# MCU.net
KiCad netlist of a schematic drawn in Altium Designer
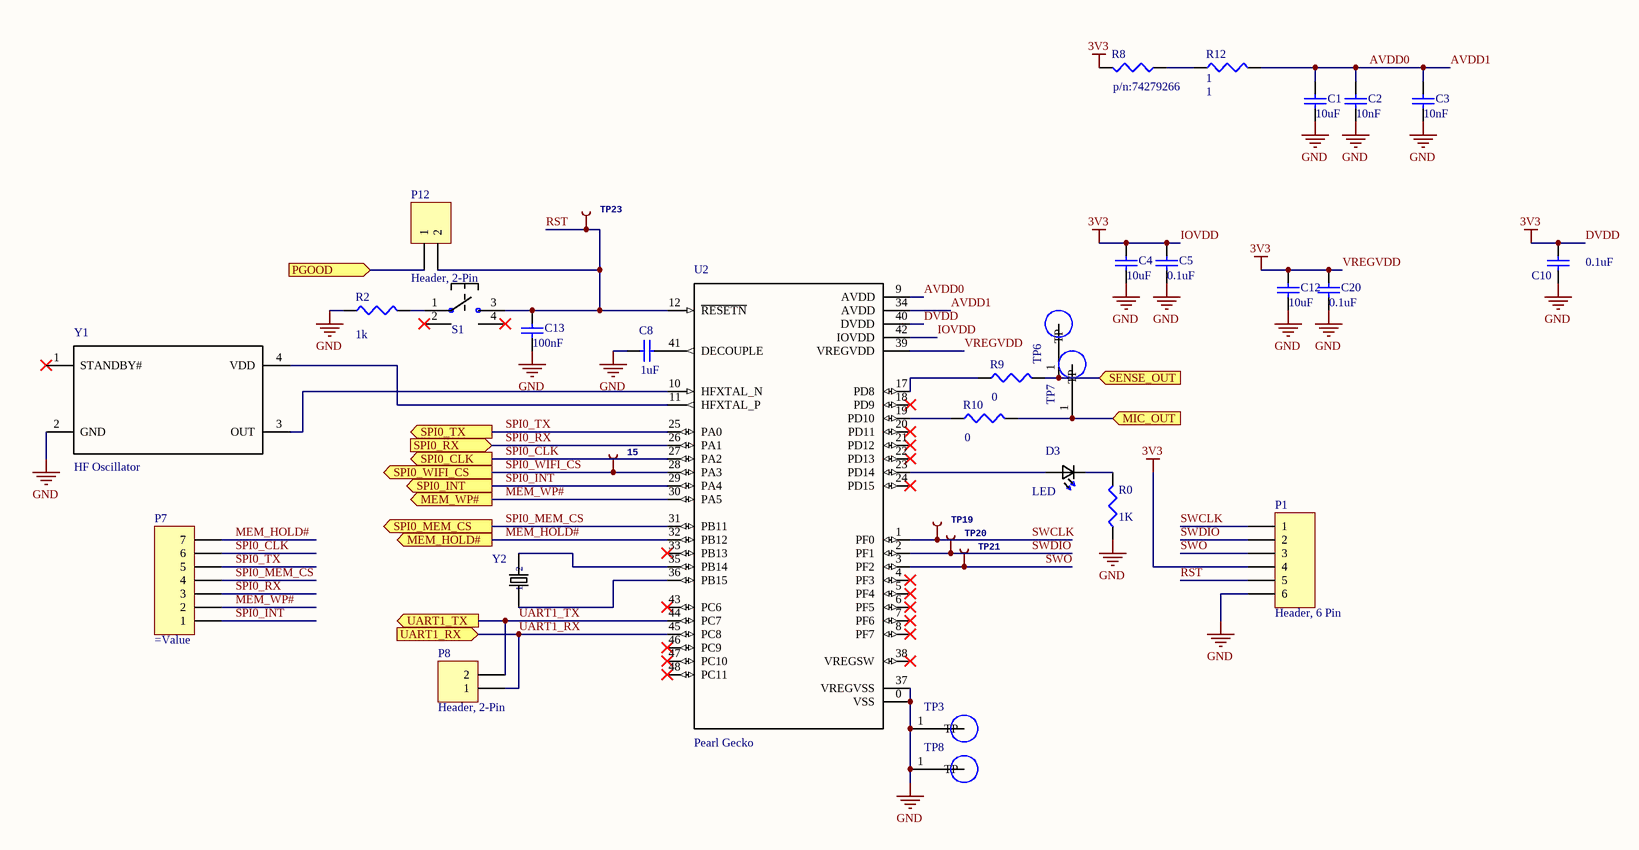
[diagram p0: MCU.SchDoc]

(export (version "E")
  (design (tool "Eeschema 10.0.6"))
  (components
    (comp (ref "15")
      (value "SparkFun Test Points")
      (footprint "PAD.02X.02")
      (libsource (lib "SparkFun-Connectors") (part "TEST-POINT2"))
    )
    (comp (ref "C1")
      (value "10uF")
      (footprint "1608[0603]")
      (description "Capacitor (Semiconductor SIM Model)")
      (fields (field (name "PUBLISHER") "Altium Limited"))
      (libsource (lib "Miscellaneous Devices") (part "Cap Semi"))
    )
    (comp (ref "C2")
      (value "10nF")
      (footprint "1608[0603]")
      (description "Capacitor (Semiconductor SIM Model)")
      (fields (field (name "PUBLISHER") "Altium Limited"))
      (libsource (lib "Miscellaneous Devices") (part "Cap Semi"))
    )
    (comp (ref "C3")
      (value "10nF")
      (footprint "1608[0603]")
      (description "Capacitor (Semiconductor SIM Model)")
      (fields (field (name "PUBLISHER") "Altium Limited"))
      (libsource (lib "Miscellaneous Devices") (part "Cap Semi"))
    )
    (comp (ref "C4")
      (value "10uF")
      (footprint "1608[0603]")
      (description "Capacitor (Semiconductor SIM Model)")
      (fields (field (name "PUBLISHER") "Altium Limited"))
      (libsource (lib "Miscellaneous Devices") (part "Cap Semi"))
    )
    (comp (ref "C5")
      (value "0.1uF")
      (footprint "1608[0603]")
      (description "Capacitor (Semiconductor SIM Model)")
      (fields (field (name "PUBLISHER") "Altium Limited"))
      (libsource (lib "Miscellaneous Devices") (part "Cap Semi"))
    )
    (comp (ref "C8")
      (value "1uF")
      (footprint "1608[0603]")
      (description "Capacitor (Semiconductor SIM Model)")
      (fields (field (name "PUBLISHER") "Altium Limited"))
      (libsource (lib "Miscellaneous Devices") (part "Cap Semi"))
    )
    (comp (ref "C10")
      (value "0.1uF")
      (footprint "1608[0603]")
      (description "Capacitor (Semiconductor SIM Model)")
      (fields (field (name "PUBLISHER") "Altium Limited"))
      (libsource (lib "Miscellaneous Devices") (part "Cap Semi"))
    )
    (comp (ref "C12")
      (value "10uF")
      (footprint "1608[0603]")
      (description "Capacitor (Semiconductor SIM Model)")
      (fields
        (field (name "MANUFACTURER") "Samsung")
        (field (name "MANUFACTURER PART NUMBER") "CL10B106MQ8NRNC")
        (field (name "PUBLISHER") "Altium Limited")
      )
      (libsource (lib "Miscellaneous Devices") (part "Cap Semi"))
    )
    (comp (ref "C13")
      (value "100nF")
      (footprint "1608[0603]")
      (description "Capacitor (Semiconductor SIM Model)")
      (fields (field (name "PUBLISHER") "Altium Limited"))
      (libsource (lib "Miscellaneous Devices") (part "Cap Semi"))
    )
    (comp (ref "C20")
      (value "0.1uF")
      (footprint "1608[0603]")
      (description "Capacitor (Semiconductor SIM Model)")
      (fields (field (name "PUBLISHER") "Altium Limited"))
      (libsource (lib "Miscellaneous Devices") (part "Cap Semi"))
    )
    (comp (ref "D3")
      (value "LED")
      (footprint "0603_TLMO1100-GS08(Primary)")
      (description "Orange 0603 160Â° 80 mcd 2.1 V 30 mA Non Diffused Surface Mount LED")
      (fields (field (name "MP") "TLMO1100-GS08") (field (name "DIGI-KEY_PART_NUMBER") "751-1174-1-ND"))
      (libsource (lib "LowPower_3ER_Parts") (part "TLMO1100-GS08"))
    )
    (comp (ref "P1")
      (value "Header, 6 Pin")
      (footprint "HDR1X6")
      (description "Header, 6-Pin")
      (fields (field (name "PUBLISHER") "Altium Limited"))
      (libsource (lib "Miscellaneous Connectors") (part "Header 6"))
    )
    (comp (ref "P7")
      (value "~")
      (footprint "HDR1X7")
      (description "Header, 7-Pin")
      (fields (field (name "PUBLISHER") "Altium Limited"))
      (libsource (lib "Miscellaneous Connectors") (part "Header 7"))
    )
    (comp (ref "P8")
      (value "Header, 2-Pin")
      (footprint "HDR1X2")
      (fields (field (name "PUBLISHER") "Altium Limited"))
      (libsource (lib "Miscellaneous Connectors") (part "Header 2"))
    )
    (comp (ref "P12")
      (value "Header, 2-Pin")
      (footprint "HDR1X2")
      (fields (field (name "PUBLISHER") "Altium Limited"))
      (libsource (lib "") (part "Header 2_1"))
    )
    (comp (ref "R0")
      (value "1K")
      (footprint "J1-0603")
      (description "Resistor")
      (fields (field (name "PUBLISHER") "Altium Limited"))
      (libsource (lib "Miscellaneous Devices") (part "Res3"))
    )
    (comp (ref "R2")
      (value "1k")
      (footprint "J1-0603")
      (description "Resistor")
      (fields (field (name "PUBLISHER") "Altium Limited"))
      (libsource (lib "Miscellaneous Devices") (part "Res3"))
    )
    (comp (ref "R8")
      (value "p/n:74279266")
      (footprint "J1-0603")
      (description "Resistor")
      (fields (field (name "Comment") "Ferrite Bead") (field (name "PUBLISHER") "Altium Limited"))
      (libsource (lib "Miscellaneous Devices") (part "Res3"))
    )
    (comp (ref "R9")
      (value "0")
      (footprint "J1-0603")
      (description "Resistor")
      (fields (field (name "PUBLISHER") "Altium Limited"))
      (libsource (lib "Miscellaneous Devices") (part "Res3"))
    )
    (comp (ref "R10")
      (value "0")
      (footprint "J1-0603")
      (description "Resistor")
      (fields (field (name "PUBLISHER") "Altium Limited"))
      (libsource (lib "Miscellaneous Devices") (part "Res3"))
    )
    (comp (ref "R12")
      (value "1")
      (footprint "J1-0603")
      (description "Resistor")
      (fields (field (name "ALTIUM_VALUE") "1") (field (name "PUBLISHER") "Altium Limited"))
      (libsource (lib "Miscellaneous Devices") (part "Res3"))
    )
    (comp (ref "S1")
      (value "Button")
      (footprint "TL3315NF100Q")
      (description "TL3315 Series SPST 1 N Round Button J-Bend SMT Low Profile Tactile Switch")
      (fields (field (name "MF") "E-Switch") (field (name "MP") "TL3315NF100Q"))
      (libsource (lib "LowPower_3ER_Parts") (part "TL3315NF100Q"))
    )
    (comp (ref "TP3")
      (value "Test Points")
      (footprint "TP380X203")
      (description "Phosphor Bronze Contact Miniature Silver Plated Surface Mount Test Points")
      (fields (field (name "MF") "Keystone") (field (name "DIGI-KEY_PART_NUMBER") "36-5019CT-ND"))
      (libsource (lib "LowPower_3ER_Parts") (part "5019"))
    )
    (comp (ref "TP6")
      (value "Test Points")
      (footprint "TP380X203")
      (description "Phosphor Bronze Contact Miniature Silver Plated Surface Mount Test Points")
      (fields (field (name "MF") "Keystone") (field (name "DIGI-KEY_PART_NUMBER") "36-5019CT-ND"))
      (libsource (lib "LowPower_3ER_Parts") (part "5019"))
    )
    (comp (ref "TP7")
      (value "Test Points")
      (footprint "TP380X203")
      (description "Phosphor Bronze Contact Miniature Silver Plated Surface Mount Test Points")
      (fields (field (name "MF") "Keystone") (field (name "DIGI-KEY_PART_NUMBER") "36-5019CT-ND"))
      (libsource (lib "LowPower_3ER_Parts") (part "5019"))
    )
    (comp (ref "TP8")
      (value "Test Points")
      (footprint "TP380X203")
      (description "Phosphor Bronze Contact Miniature Silver Plated Surface Mount Test Points")
      (fields (field (name "MF") "Keystone") (field (name "DIGI-KEY_PART_NUMBER") "36-5019CT-ND"))
      (libsource (lib "LowPower_3ER_Parts") (part "5019"))
    )
    (comp (ref "TP19")
      (value "SparkFun Test Points")
      (footprint "PAD.02X.02")
      (libsource (lib "SparkFun-Connectors") (part "TEST-POINT2"))
    )
    (comp (ref "TP20")
      (value "SparkFun Test Points")
      (footprint "PAD.02X.02")
      (libsource (lib "SparkFun-Connectors") (part "TEST-POINT2"))
    )
    (comp (ref "TP21")
      (value "SparkFun Test Points")
      (footprint "PAD.02X.02")
      (libsource (lib "SparkFun-Connectors") (part "TEST-POINT2"))
    )
    (comp (ref "TP23")
      (value "SparkFun Test Points")
      (footprint "PAD.02X.02")
      (libsource (lib "SparkFun-Connectors") (part "TEST-POINT2"))
    )
    (comp (ref "U2")
      (value "Pearl Gecko")
      (footprint "QFN50P700X700X90-49N")
      (description "MCU 32-bit ARM Cortex M4 RISC 1024KB Flash 3.3V 48-Pin QFN EP")
      (fields (field (name "MP") "EFM32PG12B500F1024GM48-B") (field (name "MF") "Silicon Labs"))
      (libsource (lib "LowPower_3ER_Parts") (part "EFM32PG12B500F1024GM48-B"))
    )
    (comp (ref "Y1")
      (value "HF Oscillator")
      (footprint "OSCSC320X250X100N")
      (description "Oscillator MEMS 40MHz ?25ppm (Stability) 15pF 55% 1.8V/2.5V/3.3V Automotive 4-Pin QFN SMD T/R")
      (fields (field (name "MF") "Abracon") (field (name "MP") "ASFLMB-40.000MHZ-LR-T"))
      (libsource (lib "LowPower_3ER_Parts") (part "ASFLMB-40.000MHZ-LR-T"))
    )
    (comp (ref "Y2")
      (value "LF Oscillator")
      (footprint "XTAL320X150X90N")
      (fields
        (field (name "MF") "ECS International")
        (field (name "DIGI-KEY_PART_NUMBER") "XC1617CT-ND")
        (field (name "MP") "ECS-.327-12.5-34B-TR")
      )
      (libsource (lib "LowPower_3ER_Parts") (part "ECS-.327-12.5-34B-TR"))
    )
  )
  (nets
    (net (code "1") (name "/AVDD0") (class "Default")
      (node (ref "C1") (pin "2") (pinfunction "2_2") (pintype "passive"))
      (node (ref "C2") (pin "2") (pinfunction "2_2") (pintype "passive"))
      (node (ref "C3") (pin "2") (pinfunction "2_2") (pintype "passive"))
      (node (ref "R12") (pin "2") (pinfunction "2_2") (pintype "passive"))
      (node (ref "U2") (pin "34") (pinfunction "AVDD_34") (pintype "power_in"))
      (node (ref "U2") (pin "9") (pinfunction "AVDD_9") (pintype "power_in"))
    )
    (net (code "2") (name "/MEM_HOLD#") (class "Default")
      (node (ref "P7") (pin "7") (pinfunction "7_7") (pintype "passive"))
      (node (ref "U2") (pin "32") (pinfunction "PB12_32") (pintype "bidirectional"))
    )
    (net (code "3") (name "/MEM_WP#") (class "Default")
      (node (ref "P7") (pin "2") (pinfunction "2_2") (pintype "passive"))
      (node (ref "U2") (pin "30") (pinfunction "PA5_30") (pintype "bidirectional"))
    )
    (net (code "4") (name "/MIC_OUT") (class "Default")
      (node (ref "R10") (pin "2") (pinfunction "2_2") (pintype "passive"))
      (node (ref "TP7") (pin "1") (pinfunction "TP_1") (pintype "passive"))
    )
    (net (code "5") (name "/PGOOD") (class "Default")
      (node (ref "P12") (pin "1") (pinfunction "1_1") (pintype "passive"))
    )
    (net (code "6") (name "/RST") (class "Default")
      (node (ref "C13") (pin "2") (pinfunction "2_2") (pintype "passive"))
      (node (ref "P1") (pin "5") (pinfunction "5_5") (pintype "passive"))
      (node (ref "P12") (pin "2") (pinfunction "2_2") (pintype "passive"))
      (node (ref "S1") (pin "3") (pinfunction "P$2_3") (pintype "passive"))
      (node (ref "TP23") (pin "P$1") (pinfunction "1_P$1") (pintype "passive"))
      (node (ref "U2") (pin "12") (pinfunction "~{RESETN}_12") (pintype "input"))
    )
    (net (code "7") (name "/SENSE_OUT") (class "Default")
      (node (ref "R9") (pin "2") (pinfunction "2_2") (pintype "passive"))
      (node (ref "TP6") (pin "1") (pinfunction "TP_1") (pintype "passive"))
    )
    (net (code "8") (name "/SPI0_CLK") (class "Default")
      (node (ref "P7") (pin "6") (pinfunction "6_6") (pintype "passive"))
      (node (ref "U2") (pin "27") (pinfunction "PA2_27") (pintype "bidirectional"))
    )
    (net (code "9") (name "/SPI0_INT") (class "Default")
      (node (ref "P7") (pin "1") (pinfunction "1_1") (pintype "passive"))
      (node (ref "U2") (pin "29") (pinfunction "PA4_29") (pintype "bidirectional"))
    )
    (net (code "10") (name "/SPI0_MEM_CS") (class "Default")
      (node (ref "P7") (pin "4") (pinfunction "4_4") (pintype "passive"))
      (node (ref "U2") (pin "31") (pinfunction "PB11_31") (pintype "bidirectional"))
    )
    (net (code "11") (name "/SPI0_RX") (class "Default")
      (node (ref "P7") (pin "3") (pinfunction "3_3") (pintype "passive"))
      (node (ref "U2") (pin "26") (pinfunction "PA1_26") (pintype "bidirectional"))
    )
    (net (code "12") (name "/SPI0_TX") (class "Default")
      (node (ref "P7") (pin "5") (pinfunction "5_5") (pintype "passive"))
      (node (ref "U2") (pin "25") (pinfunction "PA0_25") (pintype "bidirectional"))
    )
    (net (code "13") (name "/SPI0_WIFI_CS") (class "Default")
      (node (ref "15") (pin "P$1") (pinfunction "1_P$1") (pintype "passive"))
      (node (ref "U2") (pin "28") (pinfunction "PA3_28") (pintype "bidirectional"))
    )
    (net (code "14") (name "/SWCLK") (class "Default")
      (node (ref "P1") (pin "1") (pinfunction "1_1") (pintype "passive"))
      (node (ref "TP19") (pin "P$1") (pinfunction "1_P$1") (pintype "passive"))
      (node (ref "U2") (pin "1") (pinfunction "PF0_1") (pintype "bidirectional"))
    )
    (net (code "15") (name "/SWDIO") (class "Default")
      (node (ref "P1") (pin "2") (pinfunction "2_2") (pintype "passive"))
      (node (ref "TP20") (pin "P$1") (pinfunction "1_P$1") (pintype "passive"))
      (node (ref "U2") (pin "2") (pinfunction "PF1_2") (pintype "bidirectional"))
    )
    (net (code "16") (name "/SWO") (class "Default")
      (node (ref "P1") (pin "3") (pinfunction "3_3") (pintype "passive"))
      (node (ref "TP21") (pin "P$1") (pinfunction "1_P$1") (pintype "passive"))
      (node (ref "U2") (pin "3") (pinfunction "PF2_3") (pintype "bidirectional"))
    )
    (net (code "17") (name "/UART1_RX") (class "Default")
      (node (ref "P8") (pin "1") (pinfunction "1_1") (pintype "passive"))
      (node (ref "U2") (pin "45") (pinfunction "PC8_45") (pintype "bidirectional"))
    )
    (net (code "18") (name "/UART1_TX") (class "Default")
      (node (ref "P8") (pin "2") (pinfunction "2_2") (pintype "passive"))
      (node (ref "U2") (pin "44") (pinfunction "PC7_44") (pintype "bidirectional"))
    )
    (net (code "19") (name "3V3") (class "Default")
      (node (ref "C10") (pin "2") (pinfunction "2_2") (pintype "passive"))
      (node (ref "C12") (pin "2") (pinfunction "2_2") (pintype "passive"))
      (node (ref "C20") (pin "2") (pinfunction "2_2") (pintype "passive"))
      (node (ref "C4") (pin "2") (pinfunction "2_2") (pintype "passive"))
      (node (ref "C5") (pin "2") (pinfunction "2_2") (pintype "passive"))
      (node (ref "P1") (pin "4") (pinfunction "4_4") (pintype "passive"))
      (node (ref "R8") (pin "2") (pinfunction "2_2") (pintype "passive"))
      (node (ref "U2") (pin "39") (pinfunction "VREGVDD_39") (pintype "power_in"))
      (node (ref "U2") (pin "40") (pinfunction "DVDD_40") (pintype "power_in"))
      (node (ref "U2") (pin "42") (pinfunction "IOVDD_42") (pintype "power_in"))
    )
    (net (code "20") (name "GND") (class "Default")
      (node (ref "C1") (pin "1") (pinfunction "1_1") (pintype "passive"))
      (node (ref "C10") (pin "1") (pinfunction "1_1") (pintype "passive"))
      (node (ref "C12") (pin "1") (pinfunction "1_1") (pintype "passive"))
      (node (ref "C13") (pin "1") (pinfunction "1_1") (pintype "passive"))
      (node (ref "C2") (pin "1") (pinfunction "1_1") (pintype "passive"))
      (node (ref "C20") (pin "1") (pinfunction "1_1") (pintype "passive"))
      (node (ref "C3") (pin "1") (pinfunction "1_1") (pintype "passive"))
      (node (ref "C4") (pin "1") (pinfunction "1_1") (pintype "passive"))
      (node (ref "C5") (pin "1") (pinfunction "1_1") (pintype "passive"))
      (node (ref "C8") (pin "2") (pinfunction "2_2") (pintype "passive"))
      (node (ref "P1") (pin "6") (pinfunction "6_6") (pintype "passive"))
      (node (ref "R0") (pin "1") (pinfunction "1_1") (pintype "passive"))
      (node (ref "R2") (pin "1") (pinfunction "1_1") (pintype "passive"))
      (node (ref "TP3") (pin "1") (pinfunction "TP_1") (pintype "passive"))
      (node (ref "TP8") (pin "1") (pinfunction "TP_1") (pintype "passive"))
      (node (ref "U2") (pin "0") (pinfunction "VSS_0") (pintype "power_in"))
      (node (ref "U2") (pin "37") (pinfunction "VREGVSS_37") (pintype "power_in"))
      (node (ref "Y1") (pin "2") (pinfunction "GND_2") (pintype "passive"))
    )
    (net (code "21") (name "Net-(D3-A2)") (class "Default")
      (node (ref "D3") (pin "1") (pinfunction "A2_1") (pintype "passive"))
      (node (ref "U2") (pin "23") (pinfunction "PD14_23") (pintype "bidirectional"))
    )
    (net (code "22") (name "Net-(D3-K2)") (class "Default")
      (node (ref "D3") (pin "2") (pinfunction "K2_2") (pintype "passive"))
      (node (ref "R0") (pin "2") (pinfunction "2_2") (pintype "passive"))
    )
    (net (code "23") (name "Net-(R2-Pad2)") (class "Default")
      (node (ref "R2") (pin "2") (pinfunction "2_2") (pintype "passive"))
      (node (ref "S1") (pin "1") (pinfunction "P$1_1") (pintype "passive"))
    )
    (net (code "24") (name "Net-(R12-Pad1)") (class "Default")
      (node (ref "R12") (pin "1") (pinfunction "1_1") (pintype "passive"))
      (node (ref "R8") (pin "1") (pinfunction "1_1") (pintype "passive"))
    )
    (net (code "25") (name "Net-(U2-DECOUPLE)") (class "Default")
      (node (ref "C8") (pin "1") (pinfunction "1_1") (pintype "passive"))
      (node (ref "U2") (pin "41") (pinfunction "DECOUPLE_41") (pintype "output"))
    )
    (net (code "26") (name "Net-(U2-HFXTAL_N)") (class "Default")
      (node (ref "U2") (pin "10") (pinfunction "HFXTAL_N_10") (pintype "input"))
      (node (ref "Y1") (pin "3") (pinfunction "OUT_3") (pintype "passive"))
    )
    (net (code "27") (name "Net-(U2-HFXTAL_P)") (class "Default")
      (node (ref "U2") (pin "11") (pinfunction "HFXTAL_P_11") (pintype "output"))
      (node (ref "Y1") (pin "4") (pinfunction "VDD_4") (pintype "passive"))
    )
    (net (code "28") (name "Net-(U2-PB14)") (class "Default")
      (node (ref "U2") (pin "35") (pinfunction "PB14_35") (pintype "bidirectional"))
      (node (ref "Y2") (pin "2") (pinfunction "2_2") (pintype "passive"))
    )
    (net (code "29") (name "Net-(U2-PB15)") (class "Default")
      (node (ref "U2") (pin "36") (pinfunction "PB15_36") (pintype "bidirectional"))
      (node (ref "Y2") (pin "1") (pinfunction "1_1") (pintype "passive"))
    )
    (net (code "30") (name "Net-(U2-PD8)") (class "Default")
      (node (ref "R9") (pin "1") (pinfunction "1_1") (pintype "passive"))
      (node (ref "U2") (pin "17") (pinfunction "PD8_17") (pintype "bidirectional"))
    )
    (net (code "31") (name "Net-(U2-PD10)") (class "Default")
      (node (ref "R10") (pin "1") (pinfunction "1_1") (pintype "passive"))
      (node (ref "U2") (pin "19") (pinfunction "PD10_19") (pintype "bidirectional"))
    )
    (net (code "32") (name "unconnected-(S1-P$1-Pad2)") (class "Default")
      (node (ref "S1") (pin "2") (pinfunction "P$1_2") (pintype "passive+no_connect"))
    )
    (net (code "33") (name "unconnected-(S1-P$2-Pad4)") (class "Default")
      (node (ref "S1") (pin "4") (pinfunction "P$2_4") (pintype "passive+no_connect"))
    )
    (net (code "34") (name "unconnected-(U2-PB13-Pad33)") (class "Default")
      (node (ref "U2") (pin "33") (pinfunction "PB13_33") (pintype "bidirectional+no_connect"))
    )
    (net (code "35") (name "unconnected-(U2-PC6-Pad43)") (class "Default")
      (node (ref "U2") (pin "43") (pinfunction "PC6_43") (pintype "bidirectional+no_connect"))
    )
    (net (code "36") (name "unconnected-(U2-PC9-Pad46)") (class "Default")
      (node (ref "U2") (pin "46") (pinfunction "PC9_46") (pintype "bidirectional+no_connect"))
    )
    (net (code "37") (name "unconnected-(U2-PC10-Pad47)") (class "Default")
      (node (ref "U2") (pin "47") (pinfunction "PC10_47") (pintype "bidirectional+no_connect"))
    )
    (net (code "38") (name "unconnected-(U2-PC11-Pad48)") (class "Default")
      (node (ref "U2") (pin "48") (pinfunction "PC11_48") (pintype "bidirectional+no_connect"))
    )
    (net (code "39") (name "unconnected-(U2-PD9-Pad18)") (class "Default")
      (node (ref "U2") (pin "18") (pinfunction "PD9_18") (pintype "bidirectional+no_connect"))
    )
    (net (code "40") (name "unconnected-(U2-PD11-Pad20)") (class "Default")
      (node (ref "U2") (pin "20") (pinfunction "PD11_20") (pintype "bidirectional+no_connect"))
    )
    (net (code "41") (name "unconnected-(U2-PD12-Pad21)") (class "Default")
      (node (ref "U2") (pin "21") (pinfunction "PD12_21") (pintype "bidirectional+no_connect"))
    )
    (net (code "42") (name "unconnected-(U2-PD13-Pad22)") (class "Default")
      (node (ref "U2") (pin "22") (pinfunction "PD13_22") (pintype "bidirectional+no_connect"))
    )
    (net (code "43") (name "unconnected-(U2-PD15-Pad24)") (class "Default")
      (node (ref "U2") (pin "24") (pinfunction "PD15_24") (pintype "bidirectional+no_connect"))
    )
    (net (code "44") (name "unconnected-(U2-PF3-Pad4)") (class "Default")
      (node (ref "U2") (pin "4") (pinfunction "PF3_4") (pintype "bidirectional+no_connect"))
    )
    (net (code "45") (name "unconnected-(U2-PF4-Pad5)") (class "Default")
      (node (ref "U2") (pin "5") (pinfunction "PF4_5") (pintype "bidirectional+no_connect"))
    )
    (net (code "46") (name "unconnected-(U2-PF5-Pad6)") (class "Default")
      (node (ref "U2") (pin "6") (pinfunction "PF5_6") (pintype "bidirectional+no_connect"))
    )
    (net (code "47") (name "unconnected-(U2-PF6-Pad7)") (class "Default")
      (node (ref "U2") (pin "7") (pinfunction "PF6_7") (pintype "bidirectional+no_connect"))
    )
    (net (code "48") (name "unconnected-(U2-PF7-Pad8)") (class "Default")
      (node (ref "U2") (pin "8") (pinfunction "PF7_8") (pintype "bidirectional+no_connect"))
    )
    (net (code "49") (name "unconnected-(U2-VREGSW-Pad38)") (class "Default")
      (node (ref "U2") (pin "38") (pinfunction "VREGSW_38") (pintype "bidirectional+no_connect"))
    )
    (net (code "50") (name "unconnected-(Y1-STANDBY#-Pad1)") (class "Default")
      (node (ref "Y1") (pin "1") (pinfunction "STANDBY#_1") (pintype "passive+no_connect"))
    )
  )
)
